# Linelance_Schematic_page3.net
KiCad netlist of a schematic drawn in Altium Designer
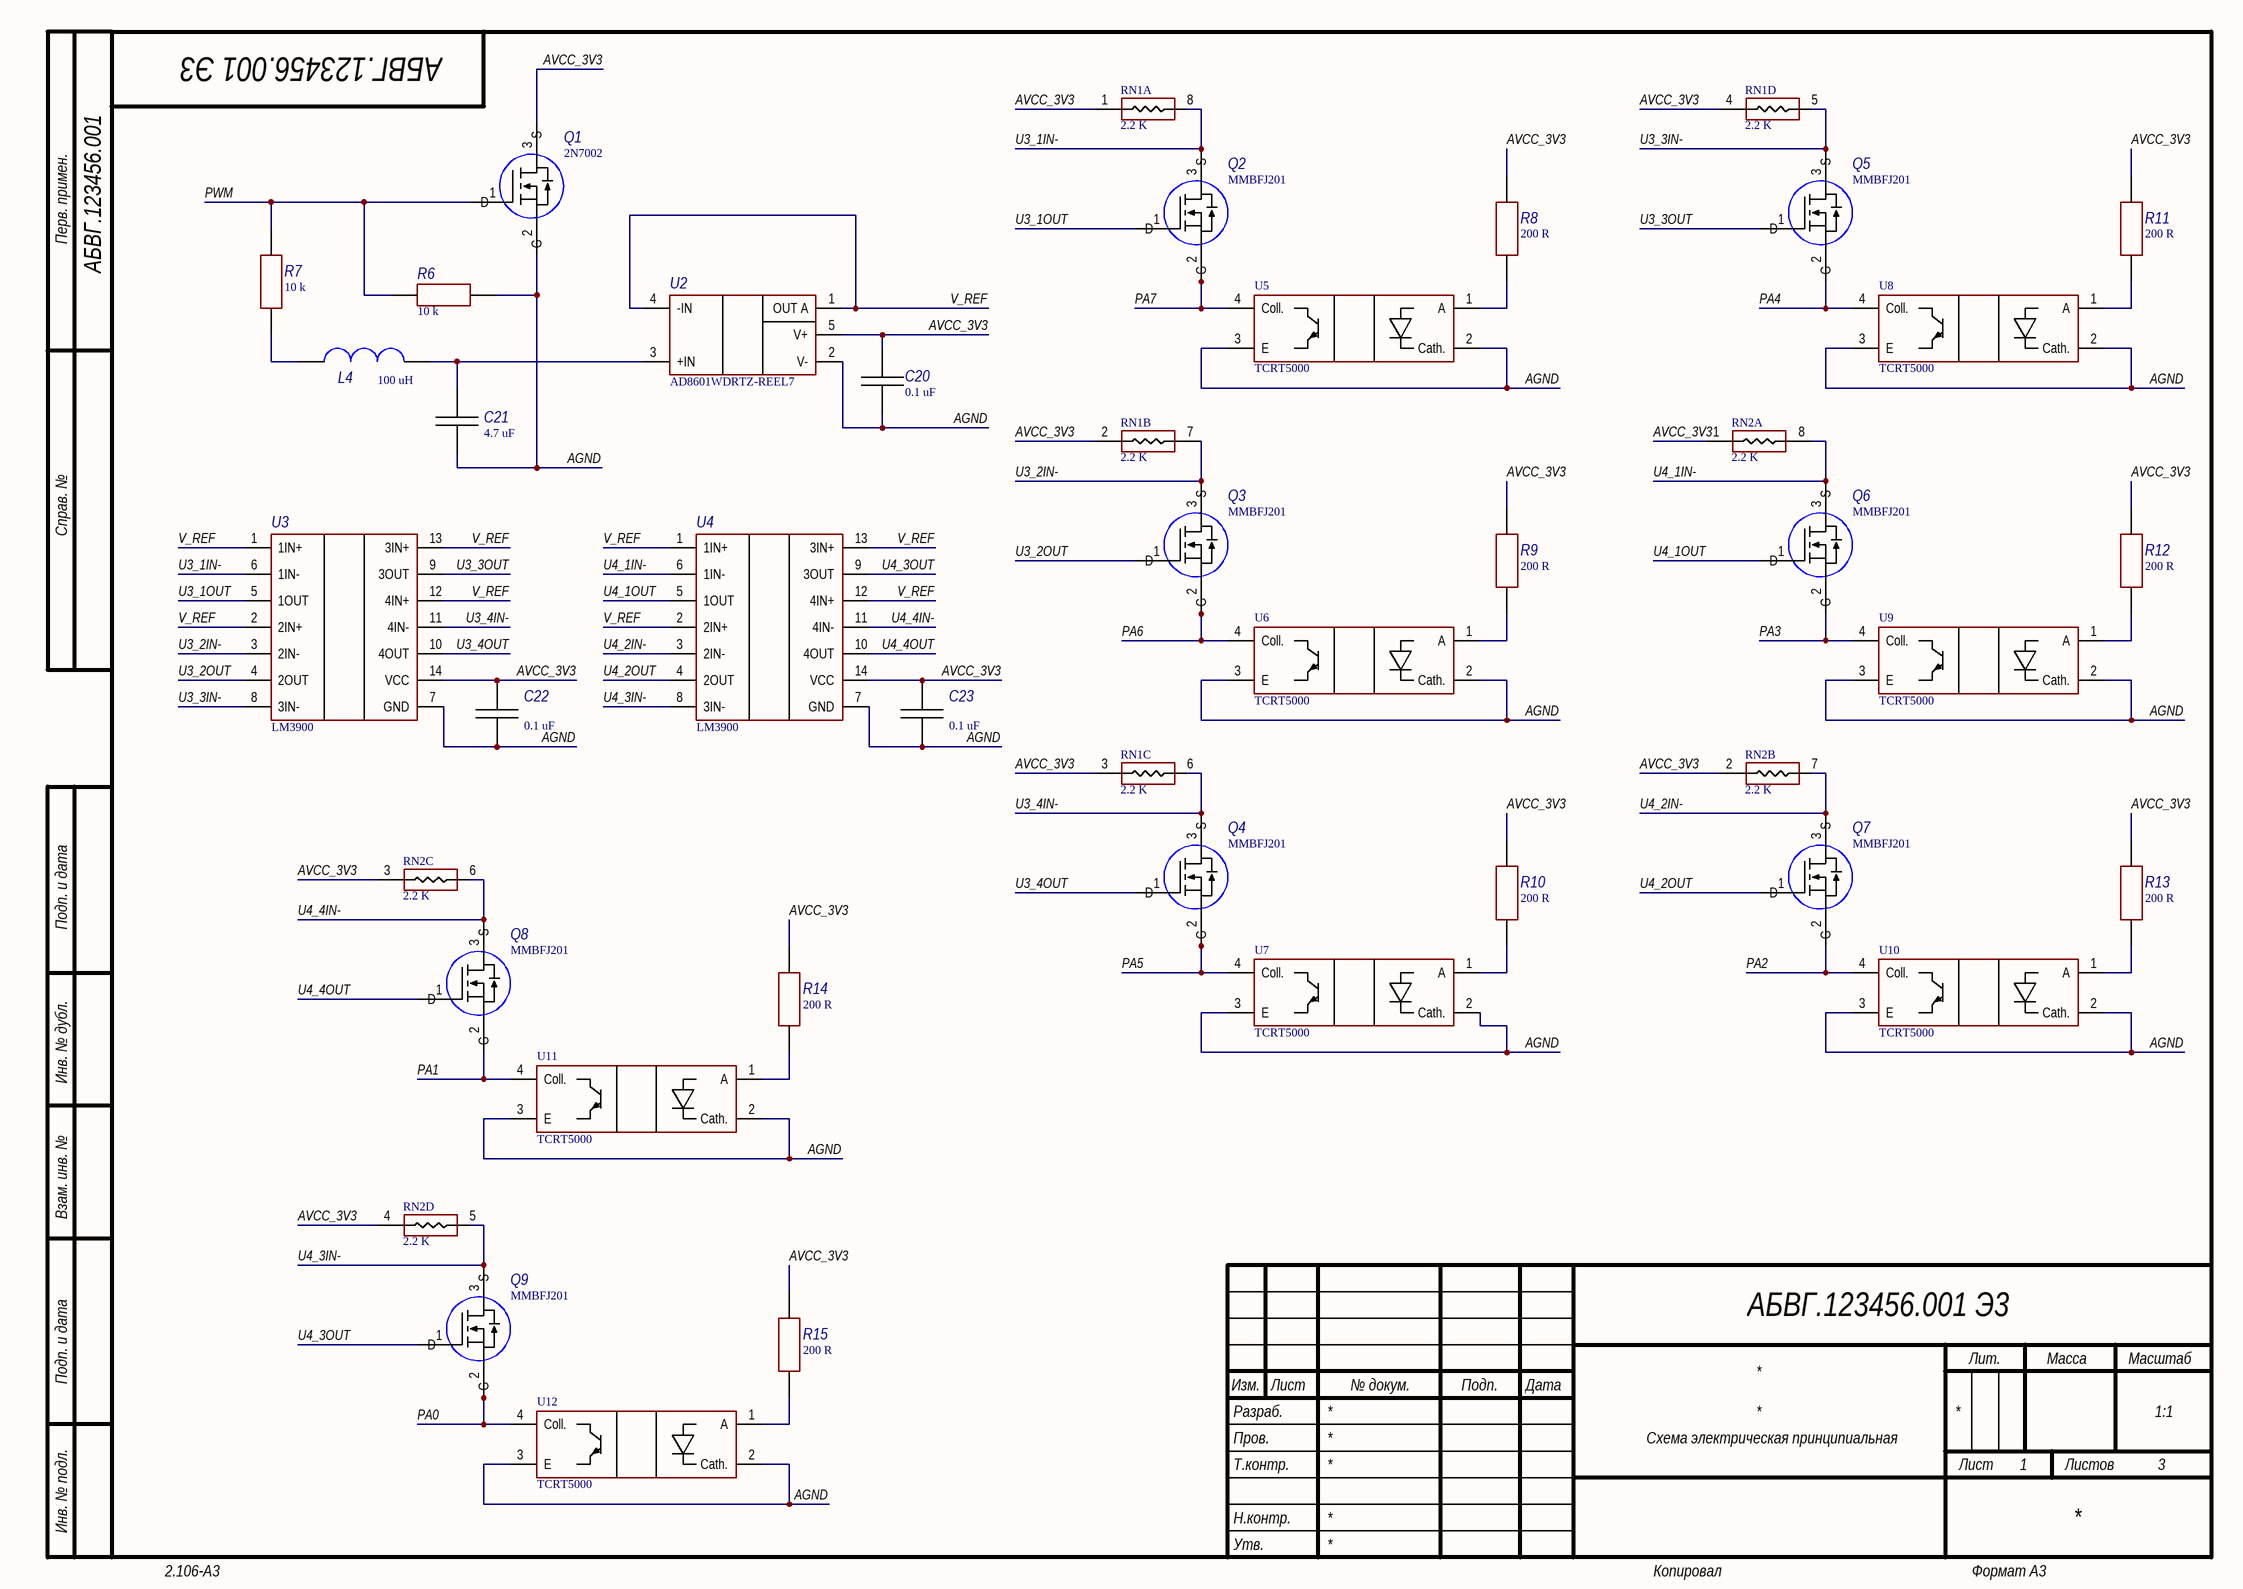
[diagram p0: Linelance_Schematic_page3.SchDoc]

(export (version "E")
  (design (tool "Eeschema 10.0.6"))
  (components
    (comp (ref "C20")
      (value "0.1 uF")
      (footprint "C0603")
      (fields (field (name "MANUFACTURER") "Murata Manufacturing"))
      (libsource (lib "Linalance_lib") (part "Capasitor"))
    )
    (comp (ref "C21")
      (value "4.7 uF")
      (footprint "C0603")
      (fields (field (name "MANUFACTURER") "Murata Manufacturing"))
      (libsource (lib "Linalance_lib") (part "Capasitor"))
    )
    (comp (ref "C22")
      (value "0.1 uF")
      (footprint "C0603")
      (fields (field (name "MANUFACTURER") "Murata Manufacturing"))
      (libsource (lib "Linalance_lib") (part "Capasitor"))
    )
    (comp (ref "C23")
      (value "0.1 uF")
      (footprint "C0603")
      (fields (field (name "MANUFACTURER") "Murata Manufacturing"))
      (libsource (lib "Linalance_lib") (part "Capasitor"))
    )
    (comp (ref "L4")
      (value "100 uH")
      (footprint "IND1206")
      (fields (field (name "MANUFACTURER") "Murata Manufacturing"))
      (libsource (lib "Linalance_lib") (part "Inductivity"))
    )
    (comp (ref "Q1")
      (value "2N7002")
      (footprint "SOT-23-3")
      (description "MOSFET N-Channel 60V 115mA (Ta) 200mW (Ta) Surface Mount SOT-23 (TO-236AB)")
      (fields (field (name "MANUFACTURER") "Vishay"))
      (libsource (lib "Linalance_lib") (part "2N7002"))
    )
    (comp (ref "Q2")
      (value "MMBFJ201")
      (footprint "SOT-23-3")
      (description "JFET N-Channel 40V 350mW Surface Mount SOT-23-3")
      (libsource (lib "Linalance_lib") (part "MMBFJ201"))
    )
    (comp (ref "Q3")
      (value "MMBFJ201")
      (footprint "SOT-23-3")
      (description "JFET N-Channel 40V 350mW Surface Mount SOT-23-3")
      (libsource (lib "Linalance_lib") (part "MMBFJ201"))
    )
    (comp (ref "Q4")
      (value "MMBFJ201")
      (footprint "SOT-23-3")
      (description "JFET N-Channel 40V 350mW Surface Mount SOT-23-3")
      (libsource (lib "Linalance_lib") (part "MMBFJ201"))
    )
    (comp (ref "Q5")
      (value "MMBFJ201")
      (footprint "SOT-23-3")
      (description "JFET N-Channel 40V 350mW Surface Mount SOT-23-3")
      (libsource (lib "Linalance_lib") (part "MMBFJ201"))
    )
    (comp (ref "Q6")
      (value "MMBFJ201")
      (footprint "SOT-23-3")
      (description "JFET N-Channel 40V 350mW Surface Mount SOT-23-3")
      (libsource (lib "Linalance_lib") (part "MMBFJ201"))
    )
    (comp (ref "Q7")
      (value "MMBFJ201")
      (footprint "SOT-23-3")
      (description "JFET N-Channel 40V 350mW Surface Mount SOT-23-3")
      (libsource (lib "Linalance_lib") (part "MMBFJ201"))
    )
    (comp (ref "Q8")
      (value "MMBFJ201")
      (footprint "SOT-23-3")
      (description "JFET N-Channel 40V 350mW Surface Mount SOT-23-3")
      (libsource (lib "Linalance_lib") (part "MMBFJ201"))
    )
    (comp (ref "Q9")
      (value "MMBFJ201")
      (footprint "SOT-23-3")
      (description "JFET N-Channel 40V 350mW Surface Mount SOT-23-3")
      (libsource (lib "Linalance_lib") (part "MMBFJ201"))
    )
    (comp (ref "R6")
      (value "10 k")
      (footprint "R0603")
      (fields (field (name "MANUFACTURER") "YAGEO"))
      (libsource (lib "") (part "Resistor_1"))
    )
    (comp (ref "R7")
      (value "10 k")
      (footprint "R0603")
      (fields (field (name "MANUFACTURER") "YAGEO"))
      (libsource (lib "Linalance_lib") (part "Resistor"))
    )
    (comp (ref "R8") (value "200 R") (footprint "R0603") (libsource (lib "Linalance_lib") (part "Resistor")))
    (comp (ref "R9") (value "200 R") (footprint "R0603") (libsource (lib "Linalance_lib") (part "Resistor")))
    (comp (ref "R10") (value "200 R") (footprint "R0603") (libsource (lib "Linalance_lib") (part "Resistor")))
    (comp (ref "R11") (value "200 R") (footprint "R0603") (libsource (lib "Linalance_lib") (part "Resistor")))
    (comp (ref "R12") (value "200 R") (footprint "R0603") (libsource (lib "Linalance_lib") (part "Resistor")))
    (comp (ref "R13") (value "200 R") (footprint "R0603") (libsource (lib "Linalance_lib") (part "Resistor")))
    (comp (ref "R14") (value "200 R") (footprint "R0603") (libsource (lib "Linalance_lib") (part "Resistor")))
    (comp (ref "R15") (value "200 R") (footprint "R0603") (libsource (lib "Linalance_lib") (part "Resistor")))
    (comp (ref "RN1")
      (value "2.2 K")
      (footprint "RN_YC164-JR-072K2L")
      (fields (field (name "MANUFACTURER") "Bourns"))
      (libsource (lib "Linalance_lib") (part "Resistor Network"))
    )
    (comp (ref "RN2")
      (value "2.2 K")
      (footprint "RN_YC164-JR-072K2L")
      (fields (field (name "MANUFACTURER") "Bourns"))
      (libsource (lib "Linalance_lib") (part "Resistor Network"))
    )
    (comp (ref "U2")
      (value "AD8601WDRTZ-REEL7")
      (footprint "SOT-23-5")
      (description "IC OPAMP GP 1 CIRCUIT SOT23-5")
      (fields (field (name "MANUFACTURER") "Analog Devices Inc."))
      (libsource (lib "Linalance_lib") (part "AD8601"))
    )
    (comp (ref "U3")
      (value "LM3900")
      (footprint "SOIC-14")
      (description "IC OPAMP GP 4 CIRCUIT 14SOIC")
      (fields (field (name "MANUFACTURER") "Texas Instruments"))
      (libsource (lib "Linalance_lib") (part "LM3900"))
    )
    (comp (ref "U4")
      (value "LM3900")
      (footprint "SOIC-14")
      (description "IC OPAMP GP 4 CIRCUIT 14SOIC")
      (fields (field (name "MANUFACTURER") "Texas Instruments"))
      (libsource (lib "Linalance_lib") (part "LM3900"))
    )
    (comp (ref "U5")
      (value "TCRT5000")
      (footprint "TCRT5000")
      (description "SENSOR OPTO TRANS 15MM REFL PCB")
      (fields (field (name "MANUFACTURER") "Vishay Semiconductor Opto Division"))
      (libsource (lib "Linalance_lib") (part "TCRT5000"))
    )
    (comp (ref "U6")
      (value "TCRT5000")
      (footprint "TCRT5000")
      (description "SENSOR OPTO TRANS 15MM REFL PCB")
      (fields (field (name "MANUFACTURER") "Vishay Semiconductor Opto Division"))
      (libsource (lib "Linalance_lib") (part "TCRT5000"))
    )
    (comp (ref "U7")
      (value "TCRT5000")
      (footprint "TCRT5000")
      (description "SENSOR OPTO TRANS 15MM REFL PCB")
      (fields (field (name "MANUFACTURER") "Vishay Semiconductor Opto Division"))
      (libsource (lib "Linalance_lib") (part "TCRT5000"))
    )
    (comp (ref "U8")
      (value "TCRT5000")
      (footprint "TCRT5000")
      (description "SENSOR OPTO TRANS 15MM REFL PCB")
      (fields (field (name "MANUFACTURER") "Vishay Semiconductor Opto Division"))
      (libsource (lib "Linalance_lib") (part "TCRT5000"))
    )
    (comp (ref "U9")
      (value "TCRT5000")
      (footprint "TCRT5000")
      (description "SENSOR OPTO TRANS 15MM REFL PCB")
      (fields (field (name "MANUFACTURER") "Vishay Semiconductor Opto Division"))
      (libsource (lib "Linalance_lib") (part "TCRT5000"))
    )
    (comp (ref "U10")
      (value "TCRT5000")
      (footprint "TCRT5000")
      (description "SENSOR OPTO TRANS 15MM REFL PCB")
      (fields (field (name "MANUFACTURER") "Vishay Semiconductor Opto Division"))
      (libsource (lib "Linalance_lib") (part "TCRT5000"))
    )
    (comp (ref "U11")
      (value "TCRT5000")
      (footprint "TCRT5000")
      (description "SENSOR OPTO TRANS 15MM REFL PCB")
      (fields (field (name "MANUFACTURER") "Vishay Semiconductor Opto Division"))
      (libsource (lib "Linalance_lib") (part "TCRT5000"))
    )
    (comp (ref "U12")
      (value "TCRT5000")
      (footprint "TCRT5000")
      (description "SENSOR OPTO TRANS 15MM REFL PCB")
      (fields (field (name "MANUFACTURER") "Vishay Semiconductor Opto Division"))
      (libsource (lib "Linalance_lib") (part "TCRT5000"))
    )
  )
  (nets
    (net (code "1") (name "/AGND") (class "Default")
      (node (ref "C20") (pin "2") (pintype "passive"))
      (node (ref "C21") (pin "2") (pintype "passive"))
      (node (ref "C22") (pin "2") (pintype "passive"))
      (node (ref "C23") (pin "2") (pintype "passive"))
      (node (ref "Q1") (pin "2") (pinfunction "G_2") (pintype "passive"))
      (node (ref "R6") (pin "2") (pintype "passive"))
      (node (ref "U10") (pin "2") (pinfunction "Cath._2") (pintype "passive"))
      (node (ref "U10") (pin "3") (pinfunction "E_3") (pintype "passive"))
      (node (ref "U11") (pin "2") (pinfunction "Cath._2") (pintype "passive"))
      (node (ref "U11") (pin "3") (pinfunction "E_3") (pintype "passive"))
      (node (ref "U12") (pin "2") (pinfunction "Cath._2") (pintype "passive"))
      (node (ref "U12") (pin "3") (pinfunction "E_3") (pintype "passive"))
      (node (ref "U2") (pin "2") (pinfunction "V-_2") (pintype "passive"))
      (node (ref "U3") (pin "7") (pinfunction "GND_7") (pintype "passive"))
      (node (ref "U4") (pin "7") (pinfunction "GND_7") (pintype "passive"))
      (node (ref "U5") (pin "2") (pinfunction "Cath._2") (pintype "passive"))
      (node (ref "U5") (pin "3") (pinfunction "E_3") (pintype "passive"))
      (node (ref "U6") (pin "2") (pinfunction "Cath._2") (pintype "passive"))
      (node (ref "U6") (pin "3") (pinfunction "E_3") (pintype "passive"))
      (node (ref "U7") (pin "2") (pinfunction "Cath._2") (pintype "passive"))
      (node (ref "U7") (pin "3") (pinfunction "E_3") (pintype "passive"))
      (node (ref "U8") (pin "2") (pinfunction "Cath._2") (pintype "passive"))
      (node (ref "U8") (pin "3") (pinfunction "E_3") (pintype "passive"))
      (node (ref "U9") (pin "2") (pinfunction "Cath._2") (pintype "passive"))
      (node (ref "U9") (pin "3") (pinfunction "E_3") (pintype "passive"))
    )
    (net (code "2") (name "/AVCC_3V3") (class "Default")
      (node (ref "C20") (pin "1") (pintype "passive"))
      (node (ref "C22") (pin "1") (pintype "passive"))
      (node (ref "C23") (pin "1") (pintype "passive"))
      (node (ref "Q1") (pin "3") (pinfunction "S_3") (pintype "passive"))
      (node (ref "R10") (pin "2") (pintype "passive"))
      (node (ref "R11") (pin "2") (pintype "passive"))
      (node (ref "R12") (pin "2") (pintype "passive"))
      (node (ref "R13") (pin "2") (pintype "passive"))
      (node (ref "R14") (pin "2") (pintype "passive"))
      (node (ref "R15") (pin "2") (pintype "passive"))
      (node (ref "R8") (pin "2") (pintype "passive"))
      (node (ref "R9") (pin "2") (pintype "passive"))
      (node (ref "RN1") (pin "1") (pintype "passive"))
      (node (ref "RN1") (pin "2") (pintype "passive"))
      (node (ref "RN1") (pin "3") (pintype "passive"))
      (node (ref "RN1") (pin "4") (pintype "passive"))
      (node (ref "RN2") (pin "1") (pintype "passive"))
      (node (ref "RN2") (pin "2") (pintype "passive"))
      (node (ref "RN2") (pin "3") (pintype "passive"))
      (node (ref "RN2") (pin "4") (pintype "passive"))
      (node (ref "U2") (pin "5") (pinfunction "V+_5") (pintype "passive"))
      (node (ref "U3") (pin "14") (pinfunction "VCC_14") (pintype "passive"))
      (node (ref "U4") (pin "14") (pinfunction "VCC_14") (pintype "passive"))
    )
    (net (code "3") (name "/PA0") (class "Default")
      (node (ref "Q9") (pin "2") (pinfunction "G_2") (pintype "passive"))
      (node (ref "U12") (pin "4") (pinfunction "Coll._4") (pintype "passive"))
    )
    (net (code "4") (name "/PA1") (class "Default")
      (node (ref "Q8") (pin "2") (pinfunction "G_2") (pintype "passive"))
      (node (ref "U11") (pin "4") (pinfunction "Coll._4") (pintype "passive"))
    )
    (net (code "5") (name "/PA2") (class "Default")
      (node (ref "Q7") (pin "2") (pinfunction "G_2") (pintype "passive"))
      (node (ref "U10") (pin "4") (pinfunction "Coll._4") (pintype "passive"))
    )
    (net (code "6") (name "/PA3") (class "Default")
      (node (ref "Q6") (pin "2") (pinfunction "G_2") (pintype "passive"))
      (node (ref "U9") (pin "4") (pinfunction "Coll._4") (pintype "passive"))
    )
    (net (code "7") (name "/PA4") (class "Default")
      (node (ref "Q5") (pin "2") (pinfunction "G_2") (pintype "passive"))
      (node (ref "U8") (pin "4") (pinfunction "Coll._4") (pintype "passive"))
    )
    (net (code "8") (name "/PA5") (class "Default")
      (node (ref "Q4") (pin "2") (pinfunction "G_2") (pintype "passive"))
      (node (ref "U7") (pin "4") (pinfunction "Coll._4") (pintype "passive"))
    )
    (net (code "9") (name "/PA6") (class "Default")
      (node (ref "Q3") (pin "2") (pinfunction "G_2") (pintype "passive"))
      (node (ref "U6") (pin "4") (pinfunction "Coll._4") (pintype "passive"))
    )
    (net (code "10") (name "/PA7") (class "Default")
      (node (ref "Q2") (pin "2") (pinfunction "G_2") (pintype "passive"))
      (node (ref "U5") (pin "4") (pinfunction "Coll._4") (pintype "passive"))
    )
    (net (code "11") (name "/PWM") (class "Default")
      (node (ref "Q1") (pin "1") (pinfunction "D_1") (pintype "passive"))
      (node (ref "R6") (pin "1") (pintype "passive"))
      (node (ref "R7") (pin "2") (pintype "passive"))
    )
    (net (code "12") (name "/U3_1IN-") (class "Default")
      (node (ref "Q2") (pin "3") (pinfunction "S_3") (pintype "passive"))
      (node (ref "RN1") (pin "8") (pintype "passive"))
      (node (ref "U3") (pin "6") (pinfunction "1IN-_6") (pintype "passive"))
    )
    (net (code "13") (name "/U3_1OUT") (class "Default")
      (node (ref "Q2") (pin "1") (pinfunction "D_1") (pintype "passive"))
      (node (ref "U3") (pin "5") (pinfunction "1OUT_5") (pintype "passive"))
    )
    (net (code "14") (name "/U3_2IN-") (class "Default")
      (node (ref "Q3") (pin "3") (pinfunction "S_3") (pintype "passive"))
      (node (ref "RN1") (pin "7") (pintype "passive"))
      (node (ref "U3") (pin "3") (pinfunction "2IN-_3") (pintype "passive"))
    )
    (net (code "15") (name "/U3_2OUT") (class "Default")
      (node (ref "Q3") (pin "1") (pinfunction "D_1") (pintype "passive"))
      (node (ref "U3") (pin "4") (pinfunction "2OUT_4") (pintype "passive"))
    )
    (net (code "16") (name "/U3_3IN-") (class "Default")
      (node (ref "Q5") (pin "3") (pinfunction "S_3") (pintype "passive"))
      (node (ref "RN1") (pin "5") (pintype "passive"))
      (node (ref "U3") (pin "8") (pinfunction "3IN-_8") (pintype "passive"))
    )
    (net (code "17") (name "/U3_3OUT") (class "Default")
      (node (ref "Q5") (pin "1") (pinfunction "D_1") (pintype "passive"))
      (node (ref "U3") (pin "9") (pinfunction "3OUT_9") (pintype "passive"))
    )
    (net (code "18") (name "/U3_4IN-") (class "Default")
      (node (ref "Q4") (pin "3") (pinfunction "S_3") (pintype "passive"))
      (node (ref "RN1") (pin "6") (pintype "passive"))
      (node (ref "U3") (pin "11") (pinfunction "4IN-_11") (pintype "passive"))
    )
    (net (code "19") (name "/U3_4OUT") (class "Default")
      (node (ref "Q4") (pin "1") (pinfunction "D_1") (pintype "passive"))
      (node (ref "U3") (pin "10") (pinfunction "4OUT_10") (pintype "passive"))
    )
    (net (code "20") (name "/U4_1IN-") (class "Default")
      (node (ref "Q6") (pin "3") (pinfunction "S_3") (pintype "passive"))
      (node (ref "RN2") (pin "8") (pintype "passive"))
      (node (ref "U4") (pin "6") (pinfunction "1IN-_6") (pintype "passive"))
    )
    (net (code "21") (name "/U4_1OUT") (class "Default")
      (node (ref "Q6") (pin "1") (pinfunction "D_1") (pintype "passive"))
      (node (ref "U4") (pin "5") (pinfunction "1OUT_5") (pintype "passive"))
    )
    (net (code "22") (name "/U4_2IN-") (class "Default")
      (node (ref "Q7") (pin "3") (pinfunction "S_3") (pintype "passive"))
      (node (ref "RN2") (pin "7") (pintype "passive"))
      (node (ref "U4") (pin "3") (pinfunction "2IN-_3") (pintype "passive"))
    )
    (net (code "23") (name "/U4_2OUT") (class "Default")
      (node (ref "Q7") (pin "1") (pinfunction "D_1") (pintype "passive"))
      (node (ref "U4") (pin "4") (pinfunction "2OUT_4") (pintype "passive"))
    )
    (net (code "24") (name "/U4_3IN-") (class "Default")
      (node (ref "Q9") (pin "3") (pinfunction "S_3") (pintype "passive"))
      (node (ref "RN2") (pin "5") (pintype "passive"))
      (node (ref "U4") (pin "8") (pinfunction "3IN-_8") (pintype "passive"))
    )
    (net (code "25") (name "/U4_3OUT") (class "Default")
      (node (ref "Q9") (pin "1") (pinfunction "D_1") (pintype "passive"))
      (node (ref "U4") (pin "9") (pinfunction "3OUT_9") (pintype "passive"))
    )
    (net (code "26") (name "/U4_4IN-") (class "Default")
      (node (ref "Q8") (pin "3") (pinfunction "S_3") (pintype "passive"))
      (node (ref "RN2") (pin "6") (pintype "passive"))
      (node (ref "U4") (pin "11") (pinfunction "4IN-_11") (pintype "passive"))
    )
    (net (code "27") (name "/U4_4OUT") (class "Default")
      (node (ref "Q8") (pin "1") (pinfunction "D_1") (pintype "passive"))
      (node (ref "U4") (pin "10") (pinfunction "4OUT_10") (pintype "passive"))
    )
    (net (code "28") (name "/V_REF") (class "Default")
      (node (ref "U2") (pin "1") (pinfunction "OUT_A_1") (pintype "passive"))
      (node (ref "U2") (pin "4") (pinfunction "-IN_4") (pintype "passive"))
      (node (ref "U3") (pin "1") (pinfunction "1IN+_1") (pintype "passive"))
      (node (ref "U3") (pin "12") (pinfunction "4IN+_12") (pintype "passive"))
      (node (ref "U3") (pin "13") (pinfunction "3IN+_13") (pintype "passive"))
      (node (ref "U3") (pin "2") (pinfunction "2IN+_2") (pintype "passive"))
      (node (ref "U4") (pin "1") (pinfunction "1IN+_1") (pintype "passive"))
      (node (ref "U4") (pin "12") (pinfunction "4IN+_12") (pintype "passive"))
      (node (ref "U4") (pin "13") (pinfunction "3IN+_13") (pintype "passive"))
      (node (ref "U4") (pin "2") (pinfunction "2IN+_2") (pintype "passive"))
    )
    (net (code "29") (name "Net-(L4-Pad1)") (class "Default")
      (node (ref "L4") (pin "1") (pintype "passive"))
      (node (ref "R7") (pin "1") (pintype "passive"))
    )
    (net (code "30") (name "Net-(U2-+IN)") (class "Default")
      (node (ref "C21") (pin "1") (pintype "passive"))
      (node (ref "L4") (pin "2") (pintype "passive"))
      (node (ref "U2") (pin "3") (pinfunction "+IN_3") (pintype "passive"))
    )
    (net (code "31") (name "Net-(U5-A)") (class "Default")
      (node (ref "R8") (pin "1") (pintype "passive"))
      (node (ref "U5") (pin "1") (pinfunction "A_1") (pintype "passive"))
    )
    (net (code "32") (name "Net-(U6-A)") (class "Default")
      (node (ref "R9") (pin "1") (pintype "passive"))
      (node (ref "U6") (pin "1") (pinfunction "A_1") (pintype "passive"))
    )
    (net (code "33") (name "Net-(U7-A)") (class "Default")
      (node (ref "R10") (pin "1") (pintype "passive"))
      (node (ref "U7") (pin "1") (pinfunction "A_1") (pintype "passive"))
    )
    (net (code "34") (name "Net-(U8-A)") (class "Default")
      (node (ref "R11") (pin "1") (pintype "passive"))
      (node (ref "U8") (pin "1") (pinfunction "A_1") (pintype "passive"))
    )
    (net (code "35") (name "Net-(U9-A)") (class "Default")
      (node (ref "R12") (pin "1") (pintype "passive"))
      (node (ref "U9") (pin "1") (pinfunction "A_1") (pintype "passive"))
    )
    (net (code "36") (name "Net-(U10-A)") (class "Default")
      (node (ref "R13") (pin "1") (pintype "passive"))
      (node (ref "U10") (pin "1") (pinfunction "A_1") (pintype "passive"))
    )
    (net (code "37") (name "Net-(U11-A)") (class "Default")
      (node (ref "R14") (pin "1") (pintype "passive"))
      (node (ref "U11") (pin "1") (pinfunction "A_1") (pintype "passive"))
    )
    (net (code "38") (name "Net-(U12-A)") (class "Default")
      (node (ref "R15") (pin "1") (pintype "passive"))
      (node (ref "U12") (pin "1") (pinfunction "A_1") (pintype "passive"))
    )
  )
)
